# STM32F446RC_double_layer.net
KiCad netlist of a schematic drawn in EAGLE
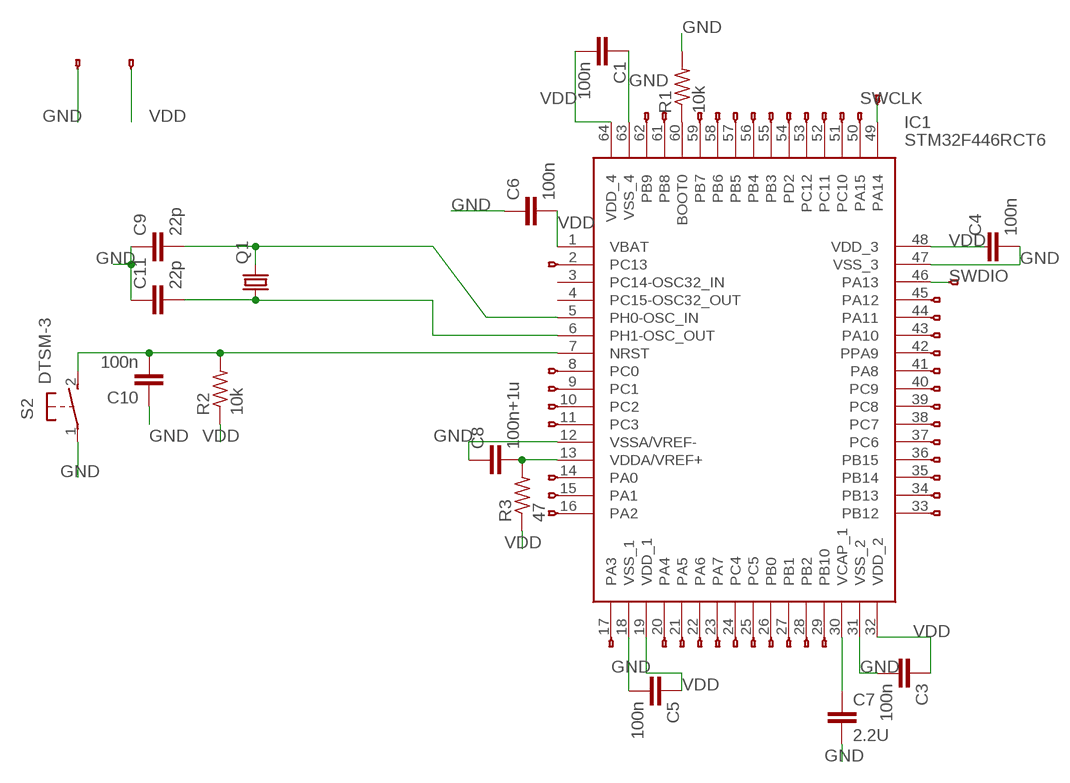
[diagram p0: schematic, sheet 1]

(export (version "E")
  (design (tool "Eeschema 10.0.6"))
  (components
    (comp (ref "C1")
      (value "100n")
      (footprint "eagle-import:C2.5-3")
      (libsource (lib "eagle-import") (part "C2,5-3"))
    )
    (comp (ref "C3")
      (value "100n")
      (footprint "eagle-import:C2.5-3")
      (libsource (lib "eagle-import") (part "C2,5-3"))
    )
    (comp (ref "C4")
      (value "100n")
      (footprint "eagle-import:C2.5-3")
      (libsource (lib "eagle-import") (part "C2,5-3"))
    )
    (comp (ref "C5")
      (value "100n")
      (footprint "eagle-import:C2.5-3")
      (libsource (lib "eagle-import") (part "C2,5-3"))
    )
    (comp (ref "C6")
      (value "100n")
      (footprint "eagle-import:C2.5-3")
      (libsource (lib "eagle-import") (part "C2,5-3"))
    )
    (comp (ref "C7")
      (value "2.2U")
      (footprint "eagle-import:C2.5-3")
      (libsource (lib "eagle-import") (part "C2,5-3"))
    )
    (comp (ref "C8")
      (value "100n+1u")
      (footprint "eagle-import:C2.5-3")
      (libsource (lib "eagle-import") (part "C2,5-3"))
    )
    (comp (ref "C9")
      (value "22p")
      (footprint "eagle-import:C2.5-3")
      (libsource (lib "eagle-import") (part "C2,5-3"))
    )
    (comp (ref "C10")
      (value "100n")
      (footprint "eagle-import:C2.5-3")
      (libsource (lib "eagle-import") (part "C2,5-3"))
    )
    (comp (ref "C11")
      (value "22p")
      (footprint "eagle-import:C2.5-3")
      (libsource (lib "eagle-import") (part "C2,5-3"))
    )
    (comp (ref "IC1")
      (value "STM32F446RCT6")
      (footprint "eagle-import:QFP50P1200X1200X160-64N")
      (fields (field (name "MOUSER_PART_NUMBER") "511-STM32F446RCT6"))
      (libsource (lib "eagle-import") (part "STM32F446RCT6"))
    )
    (comp (ref "JP1")
      (value "HEADERHOLE-HEADERHOLE")
      (footprint "eagle-import:1X1-HEADER-HOLE")
      (libsource (lib "eagle-import") (part "HEADERHOLE-HEADERHOLE"))
    )
    (comp (ref "JP2")
      (value "HEADERHOLE-HEADERHOLE")
      (footprint "eagle-import:1X1-HEADER-HOLE")
      (libsource (lib "eagle-import") (part "HEADERHOLE-HEADERHOLE"))
    )
    (comp (ref "JP3")
      (value "HEADERHOLE-HEADERHOLE")
      (footprint "eagle-import:1X1-HEADER-HOLE")
      (libsource (lib "eagle-import") (part "HEADERHOLE-HEADERHOLE"))
    )
    (comp (ref "JP4")
      (value "HEADERHOLE-HEADERHOLE")
      (footprint "eagle-import:1X1-HEADER-HOLE")
      (libsource (lib "eagle-import") (part "HEADERHOLE-HEADERHOLE"))
    )
    (comp (ref "JP5")
      (value "HEADERHOLE-HEADERHOLE")
      (footprint "eagle-import:1X1-HEADER-HOLE")
      (libsource (lib "eagle-import") (part "HEADERHOLE-HEADERHOLE"))
    )
    (comp (ref "JP6")
      (value "HEADERHOLE-HEADERHOLE")
      (footprint "eagle-import:1X1-HEADER-HOLE")
      (libsource (lib "eagle-import") (part "HEADERHOLE-HEADERHOLE"))
    )
    (comp (ref "JP7")
      (value "HEADERHOLE-HEADERHOLE")
      (footprint "eagle-import:1X1-HEADER-HOLE")
      (libsource (lib "eagle-import") (part "HEADERHOLE-HEADERHOLE"))
    )
    (comp (ref "JP8")
      (value "HEADERHOLE-HEADERHOLE")
      (footprint "eagle-import:1X1-HEADER-HOLE")
      (libsource (lib "eagle-import") (part "HEADERHOLE-HEADERHOLE"))
    )
    (comp (ref "JP9")
      (value "HEADERHOLE-HEADERHOLE")
      (footprint "eagle-import:1X1-HEADER-HOLE")
      (libsource (lib "eagle-import") (part "HEADERHOLE-HEADERHOLE"))
    )
    (comp (ref "JP10")
      (value "HEADERHOLE-HEADERHOLE")
      (footprint "eagle-import:1X1-HEADER-HOLE")
      (libsource (lib "eagle-import") (part "HEADERHOLE-HEADERHOLE"))
    )
    (comp (ref "JP11")
      (value "HEADERHOLE-HEADERHOLE")
      (footprint "eagle-import:1X1-HEADER-HOLE")
      (libsource (lib "eagle-import") (part "HEADERHOLE-HEADERHOLE"))
    )
    (comp (ref "JP12")
      (value "HEADERHOLE-HEADERHOLE")
      (footprint "eagle-import:1X1-HEADER-HOLE")
      (libsource (lib "eagle-import") (part "HEADERHOLE-HEADERHOLE"))
    )
    (comp (ref "JP13")
      (value "HEADERHOLE-HEADERHOLE")
      (footprint "eagle-import:1X1-HEADER-HOLE")
      (libsource (lib "eagle-import") (part "HEADERHOLE-HEADERHOLE"))
    )
    (comp (ref "JP14")
      (value "HEADERHOLE-HEADERHOLE")
      (footprint "eagle-import:1X1-HEADER-HOLE")
      (libsource (lib "eagle-import") (part "HEADERHOLE-HEADERHOLE"))
    )
    (comp (ref "JP15")
      (value "HEADERHOLE-HEADERHOLE")
      (footprint "eagle-import:1X1-HEADER-HOLE")
      (libsource (lib "eagle-import") (part "HEADERHOLE-HEADERHOLE"))
    )
    (comp (ref "JP16")
      (value "HEADERHOLE-HEADERHOLE")
      (footprint "eagle-import:1X1-HEADER-HOLE")
      (libsource (lib "eagle-import") (part "HEADERHOLE-HEADERHOLE"))
    )
    (comp (ref "JP17")
      (value "HEADERHOLE-HEADERHOLE")
      (footprint "eagle-import:1X1-HEADER-HOLE")
      (libsource (lib "eagle-import") (part "HEADERHOLE-HEADERHOLE"))
    )
    (comp (ref "JP18")
      (value "HEADERHOLE-HEADERHOLE")
      (footprint "eagle-import:1X1-HEADER-HOLE")
      (libsource (lib "eagle-import") (part "HEADERHOLE-HEADERHOLE"))
    )
    (comp (ref "JP19")
      (value "HEADERHOLE-HEADERHOLE")
      (footprint "eagle-import:1X1-HEADER-HOLE")
      (libsource (lib "eagle-import") (part "HEADERHOLE-HEADERHOLE"))
    )
    (comp (ref "JP21")
      (value "HEADERHOLE-HEADERHOLE")
      (footprint "eagle-import:1X1-HEADER-HOLE")
      (libsource (lib "eagle-import") (part "HEADERHOLE-HEADERHOLE"))
    )
    (comp (ref "JP22")
      (value "HEADERHOLE-HEADERHOLE")
      (footprint "eagle-import:1X1-HEADER-HOLE")
      (libsource (lib "eagle-import") (part "HEADERHOLE-HEADERHOLE"))
    )
    (comp (ref "JP23")
      (value "HEADERHOLE-HEADERHOLE")
      (footprint "eagle-import:1X1-HEADER-HOLE")
      (libsource (lib "eagle-import") (part "HEADERHOLE-HEADERHOLE"))
    )
    (comp (ref "JP24")
      (value "HEADERHOLE-HEADERHOLE")
      (footprint "eagle-import:1X1-HEADER-HOLE")
      (libsource (lib "eagle-import") (part "HEADERHOLE-HEADERHOLE"))
    )
    (comp (ref "JP25")
      (value "HEADERHOLE-HEADERHOLE")
      (footprint "eagle-import:1X1-HEADER-HOLE")
      (libsource (lib "eagle-import") (part "HEADERHOLE-HEADERHOLE"))
    )
    (comp (ref "JP26")
      (value "HEADERHOLE-HEADERHOLE")
      (footprint "eagle-import:1X1-HEADER-HOLE")
      (libsource (lib "eagle-import") (part "HEADERHOLE-HEADERHOLE"))
    )
    (comp (ref "JP27")
      (value "HEADERHOLE-HEADERHOLE")
      (footprint "eagle-import:1X1-HEADER-HOLE")
      (libsource (lib "eagle-import") (part "HEADERHOLE-HEADERHOLE"))
    )
    (comp (ref "JP28")
      (value "HEADERHOLE-HEADERHOLE")
      (footprint "eagle-import:1X1-HEADER-HOLE")
      (libsource (lib "eagle-import") (part "HEADERHOLE-HEADERHOLE"))
    )
    (comp (ref "JP29")
      (value "HEADERHOLE-HEADERHOLE")
      (footprint "eagle-import:1X1-HEADER-HOLE")
      (libsource (lib "eagle-import") (part "HEADERHOLE-HEADERHOLE"))
    )
    (comp (ref "JP30")
      (value "HEADERHOLE-HEADERHOLE")
      (footprint "eagle-import:1X1-HEADER-HOLE")
      (libsource (lib "eagle-import") (part "HEADERHOLE-HEADERHOLE"))
    )
    (comp (ref "JP31")
      (value "HEADERHOLE-HEADERHOLE")
      (footprint "eagle-import:1X1-HEADER-HOLE")
      (libsource (lib "eagle-import") (part "HEADERHOLE-HEADERHOLE"))
    )
    (comp (ref "JP32")
      (value "HEADERHOLE-HEADERHOLE")
      (footprint "eagle-import:1X1-HEADER-HOLE")
      (libsource (lib "eagle-import") (part "HEADERHOLE-HEADERHOLE"))
    )
    (comp (ref "JP33")
      (value "HEADERHOLE-HEADERHOLE")
      (footprint "eagle-import:1X1-HEADER-HOLE")
      (libsource (lib "eagle-import") (part "HEADERHOLE-HEADERHOLE"))
    )
    (comp (ref "JP34")
      (value "HEADERHOLE-HEADERHOLE")
      (footprint "eagle-import:1X1-HEADER-HOLE")
      (libsource (lib "eagle-import") (part "HEADERHOLE-HEADERHOLE"))
    )
    (comp (ref "JP35")
      (value "HEADERHOLE-HEADERHOLE")
      (footprint "eagle-import:1X1-HEADER-HOLE")
      (libsource (lib "eagle-import") (part "HEADERHOLE-HEADERHOLE"))
    )
    (comp (ref "JP36")
      (value "HEADERHOLE-HEADERHOLE")
      (footprint "eagle-import:1X1-HEADER-HOLE")
      (libsource (lib "eagle-import") (part "HEADERHOLE-HEADERHOLE"))
    )
    (comp (ref "JP37")
      (value "HEADERHOLE-HEADERHOLE")
      (footprint "eagle-import:1X1-HEADER-HOLE")
      (libsource (lib "eagle-import") (part "HEADERHOLE-HEADERHOLE"))
    )
    (comp (ref "JP38")
      (value "HEADERHOLE-HEADERHOLE")
      (footprint "eagle-import:1X1-HEADER-HOLE")
      (libsource (lib "eagle-import") (part "HEADERHOLE-HEADERHOLE"))
    )
    (comp (ref "JP39")
      (value "HEADERHOLE-HEADERHOLE")
      (footprint "eagle-import:1X1-HEADER-HOLE")
      (libsource (lib "eagle-import") (part "HEADERHOLE-HEADERHOLE"))
    )
    (comp (ref "JP40")
      (value "HEADERHOLE-HEADERHOLE")
      (footprint "eagle-import:1X1-HEADER-HOLE")
      (libsource (lib "eagle-import") (part "HEADERHOLE-HEADERHOLE"))
    )
    (comp (ref "JP41")
      (value "HEADERHOLE-HEADERHOLE")
      (footprint "eagle-import:1X1-HEADER-HOLE")
      (libsource (lib "eagle-import") (part "HEADERHOLE-HEADERHOLE"))
    )
    (comp (ref "JP42")
      (value "HEADERHOLE-HEADERHOLE")
      (footprint "eagle-import:1X1-HEADER-HOLE")
      (libsource (lib "eagle-import") (part "HEADERHOLE-HEADERHOLE"))
    )
    (comp (ref "JP43")
      (value "HEADERHOLE-HEADERHOLE")
      (footprint "eagle-import:1X1-HEADER-HOLE")
      (libsource (lib "eagle-import") (part "HEADERHOLE-HEADERHOLE"))
    )
    (comp (ref "JP44")
      (value "HEADERHOLE-HEADERHOLE")
      (footprint "eagle-import:1X1-HEADER-HOLE")
      (libsource (lib "eagle-import") (part "HEADERHOLE-HEADERHOLE"))
    )
    (comp (ref "JP45")
      (value "HEADERHOLE-HEADERHOLE")
      (footprint "eagle-import:1X1-HEADER-HOLE")
      (libsource (lib "eagle-import") (part "HEADERHOLE-HEADERHOLE"))
    )
    (comp (ref "JP46")
      (value "HEADERHOLE-HEADERHOLE")
      (footprint "eagle-import:1X1-HEADER-HOLE")
      (libsource (lib "eagle-import") (part "HEADERHOLE-HEADERHOLE"))
    )
    (comp (ref "JP47")
      (value "HEADERHOLE-HEADERHOLE")
      (footprint "eagle-import:1X1-HEADER-HOLE")
      (libsource (lib "eagle-import") (part "HEADERHOLE-HEADERHOLE"))
    )
    (comp (ref "JP54")
      (value "HEADERHOLE-HEADERHOLE")
      (footprint "eagle-import:1X1-HEADER-HOLE")
      (libsource (lib "eagle-import") (part "HEADERHOLE-HEADERHOLE"))
    )
    (comp (ref "JP55")
      (value "HEADERHOLE-HEADERHOLE")
      (footprint "eagle-import:1X1-HEADER-HOLE")
      (libsource (lib "eagle-import") (part "HEADERHOLE-HEADERHOLE"))
    )
    (comp (ref "Q1")
      (value "CRYSTALHC49S")
      (footprint "eagle-import:HC49_S")
      (libsource (lib "eagle-import") (part "CRYSTALHC49S"))
    )
    (comp (ref "R1")
      (value "10k")
      (footprint "eagle-import:0204V")
      (libsource (lib "eagle-import") (part "R-US_0204/2V"))
    )
    (comp (ref "R2")
      (value "10k")
      (footprint "eagle-import:0204V")
      (libsource (lib "eagle-import") (part "R-US_0204/2V"))
    )
    (comp (ref "R3")
      (value "47")
      (footprint "eagle-import:0204V")
      (libsource (lib "eagle-import") (part "R-US_0204/2V"))
    )
    (comp (ref "S2")
      (value "DTSM-3")
      (footprint "eagle-import:DTSM-3")
      (libsource (lib "eagle-import") (part "DTSM-3"))
    )
  )
  (nets
    (net (code "1") (name "/GND") (class "Default")
      (node (ref "C1") (pin "1") (pinfunction "1_1") (pintype "passive"))
      (node (ref "C10") (pin "1") (pinfunction "1_1") (pintype "passive"))
      (node (ref "C11") (pin "1") (pinfunction "1_1") (pintype "passive"))
      (node (ref "C3") (pin "2") (pinfunction "2_2") (pintype "passive"))
      (node (ref "C4") (pin "2") (pinfunction "2_2") (pintype "passive"))
      (node (ref "C5") (pin "2") (pinfunction "2_2") (pintype "passive"))
      (node (ref "C6") (pin "1") (pinfunction "1_1") (pintype "passive"))
      (node (ref "C7") (pin "2") (pinfunction "2_2") (pintype "passive"))
      (node (ref "C8") (pin "1") (pinfunction "1_1") (pintype "passive"))
      (node (ref "C9") (pin "1") (pinfunction "1_1") (pintype "passive"))
      (node (ref "IC1") (pin "12") (pinfunction "VSSA/VREF-_12") (pintype "bidirectional"))
      (node (ref "IC1") (pin "18") (pinfunction "VSS_1_18") (pintype "bidirectional"))
      (node (ref "IC1") (pin "31") (pinfunction "VSS_2_31") (pintype "bidirectional"))
      (node (ref "IC1") (pin "47") (pinfunction "VSS_3_47") (pintype "bidirectional"))
      (node (ref "IC1") (pin "63") (pinfunction "VSS_4_63") (pintype "bidirectional"))
      (node (ref "JP7") (pin "1") (pinfunction "P$1_1") (pintype "bidirectional"))
      (node (ref "R1") (pin "2") (pinfunction "2_2") (pintype "passive"))
      (node (ref "S2") (pin "1") (pinfunction "1_1") (pintype "passive"))
    )
    (net (code "2") (name "/SWCLK") (class "Default")
      (node (ref "IC1") (pin "49") (pinfunction "PA14_49") (pintype "bidirectional"))
      (node (ref "JP55") (pin "1") (pinfunction "P$1_1") (pintype "bidirectional"))
    )
    (net (code "3") (name "/SWDIO") (class "Default")
      (node (ref "IC1") (pin "46") (pinfunction "PA13_46") (pintype "bidirectional"))
      (node (ref "JP54") (pin "1") (pinfunction "P$1_1") (pintype "bidirectional"))
    )
    (net (code "4") (name "/VDD") (class "Default")
      (node (ref "C1") (pin "2") (pinfunction "2_2") (pintype "passive"))
      (node (ref "C3") (pin "1") (pinfunction "1_1") (pintype "passive"))
      (node (ref "C4") (pin "1") (pinfunction "1_1") (pintype "passive"))
      (node (ref "C5") (pin "1") (pinfunction "1_1") (pintype "passive"))
      (node (ref "C6") (pin "2") (pinfunction "2_2") (pintype "passive"))
      (node (ref "IC1") (pin "1") (pinfunction "VBAT_1") (pintype "bidirectional"))
      (node (ref "IC1") (pin "19") (pinfunction "VDD_1_19") (pintype "bidirectional"))
      (node (ref "IC1") (pin "32") (pinfunction "VDD_2_32") (pintype "bidirectional"))
      (node (ref "IC1") (pin "48") (pinfunction "VDD_3_48") (pintype "bidirectional"))
      (node (ref "IC1") (pin "64") (pinfunction "VDD_4_64") (pintype "bidirectional"))
      (node (ref "JP8") (pin "1") (pinfunction "P$1_1") (pintype "bidirectional"))
      (node (ref "R2") (pin "1") (pinfunction "1_1") (pintype "passive"))
      (node (ref "R3") (pin "1") (pinfunction "1_1") (pintype "passive"))
    )
    (net (code "5") (name "Net-(IC1-BOOT0)") (class "Default")
      (node (ref "IC1") (pin "60") (pinfunction "BOOT0_60") (pintype "bidirectional"))
      (node (ref "R1") (pin "1") (pinfunction "1_1") (pintype "passive"))
    )
    (net (code "6") (name "Net-(IC1-NRST)") (class "Default")
      (node (ref "C10") (pin "2") (pinfunction "2_2") (pintype "passive"))
      (node (ref "IC1") (pin "7") (pinfunction "NRST_7") (pintype "bidirectional"))
      (node (ref "R2") (pin "2") (pinfunction "2_2") (pintype "passive"))
      (node (ref "S2") (pin "2") (pinfunction "2_2") (pintype "passive"))
    )
    (net (code "7") (name "Net-(IC1-PA0)") (class "Default")
      (node (ref "IC1") (pin "14") (pinfunction "PA0_14") (pintype "bidirectional"))
      (node (ref "JP34") (pin "1") (pinfunction "P$1_1") (pintype "bidirectional"))
    )
    (net (code "8") (name "Net-(IC1-PA1)") (class "Default")
      (node (ref "IC1") (pin "15") (pinfunction "PA1_15") (pintype "bidirectional"))
      (node (ref "JP35") (pin "1") (pinfunction "P$1_1") (pintype "bidirectional"))
    )
    (net (code "9") (name "Net-(IC1-PA2)") (class "Default")
      (node (ref "IC1") (pin "16") (pinfunction "PA2_16") (pintype "bidirectional"))
      (node (ref "JP36") (pin "1") (pinfunction "P$1_1") (pintype "bidirectional"))
    )
    (net (code "10") (name "Net-(IC1-PA3)") (class "Default")
      (node (ref "IC1") (pin "17") (pinfunction "PA3_17") (pintype "bidirectional"))
      (node (ref "JP24") (pin "1") (pinfunction "P$1_1") (pintype "bidirectional"))
    )
    (net (code "11") (name "Net-(IC1-PA4)") (class "Default")
      (node (ref "IC1") (pin "20") (pinfunction "PA4_20") (pintype "bidirectional"))
      (node (ref "JP21") (pin "1") (pinfunction "P$1_1") (pintype "bidirectional"))
    )
    (net (code "12") (name "Net-(IC1-PA5)") (class "Default")
      (node (ref "IC1") (pin "21") (pinfunction "PA5_21") (pintype "bidirectional"))
      (node (ref "JP19") (pin "1") (pinfunction "P$1_1") (pintype "bidirectional"))
    )
    (net (code "13") (name "Net-(IC1-PA6)") (class "Default")
      (node (ref "IC1") (pin "22") (pinfunction "PA6_22") (pintype "bidirectional"))
      (node (ref "JP9") (pin "1") (pinfunction "P$1_1") (pintype "bidirectional"))
    )
    (net (code "14") (name "Net-(IC1-PA7)") (class "Default")
      (node (ref "IC1") (pin "23") (pinfunction "PA7_23") (pintype "bidirectional"))
      (node (ref "JP11") (pin "1") (pinfunction "P$1_1") (pintype "bidirectional"))
    )
    (net (code "15") (name "Net-(IC1-PA8)") (class "Default")
      (node (ref "IC1") (pin "41") (pinfunction "PA8_41") (pintype "bidirectional"))
      (node (ref "JP28") (pin "1") (pinfunction "P$1_1") (pintype "bidirectional"))
    )
    (net (code "16") (name "Net-(IC1-PA10)") (class "Default")
      (node (ref "IC1") (pin "43") (pinfunction "PA10_43") (pintype "bidirectional"))
      (node (ref "JP33") (pin "1") (pinfunction "P$1_1") (pintype "bidirectional"))
    )
    (net (code "17") (name "Net-(IC1-PA11)") (class "Default")
      (node (ref "IC1") (pin "44") (pinfunction "PA11_44") (pintype "bidirectional"))
      (node (ref "JP32") (pin "1") (pinfunction "P$1_1") (pintype "bidirectional"))
    )
    (net (code "18") (name "Net-(IC1-PA12)") (class "Default")
      (node (ref "IC1") (pin "45") (pinfunction "PA12_45") (pintype "bidirectional"))
      (node (ref "JP25") (pin "1") (pinfunction "P$1_1") (pintype "bidirectional"))
    )
    (net (code "19") (name "Net-(IC1-PA15)") (class "Default")
      (node (ref "IC1") (pin "50") (pinfunction "PA15_50") (pintype "bidirectional"))
      (node (ref "JP45") (pin "1") (pinfunction "P$1_1") (pintype "bidirectional"))
    )
    (net (code "20") (name "Net-(IC1-PB0)") (class "Default")
      (node (ref "IC1") (pin "26") (pinfunction "PB0_26") (pintype "bidirectional"))
      (node (ref "JP22") (pin "1") (pinfunction "P$1_1") (pintype "bidirectional"))
    )
    (net (code "21") (name "Net-(IC1-PB1)") (class "Default")
      (node (ref "IC1") (pin "27") (pinfunction "PB1_27") (pintype "bidirectional"))
      (node (ref "JP17") (pin "1") (pinfunction "P$1_1") (pintype "bidirectional"))
    )
    (net (code "22") (name "Net-(IC1-PB2)") (class "Default")
      (node (ref "IC1") (pin "28") (pinfunction "PB2_28") (pintype "bidirectional"))
      (node (ref "JP16") (pin "1") (pinfunction "P$1_1") (pintype "bidirectional"))
    )
    (net (code "23") (name "Net-(IC1-PB3)") (class "Default")
      (node (ref "IC1") (pin "55") (pinfunction "PB3_55") (pintype "bidirectional"))
      (node (ref "JP44") (pin "1") (pinfunction "P$1_1") (pintype "bidirectional"))
    )
    (net (code "24") (name "Net-(IC1-PB4)") (class "Default")
      (node (ref "IC1") (pin "56") (pinfunction "PB4_56") (pintype "bidirectional"))
      (node (ref "JP40") (pin "1") (pinfunction "P$1_1") (pintype "bidirectional"))
    )
    (net (code "25") (name "Net-(IC1-PB5)") (class "Default")
      (node (ref "IC1") (pin "57") (pinfunction "PB5_57") (pintype "bidirectional"))
      (node (ref "JP41") (pin "1") (pinfunction "P$1_1") (pintype "bidirectional"))
    )
    (net (code "26") (name "Net-(IC1-PB6)") (class "Default")
      (node (ref "IC1") (pin "58") (pinfunction "PB6_58") (pintype "bidirectional"))
      (node (ref "JP42") (pin "1") (pinfunction "P$1_1") (pintype "bidirectional"))
    )
    (net (code "27") (name "Net-(IC1-PB7)") (class "Default")
      (node (ref "IC1") (pin "59") (pinfunction "PB7_59") (pintype "bidirectional"))
      (node (ref "JP43") (pin "1") (pinfunction "P$1_1") (pintype "bidirectional"))
    )
    (net (code "28") (name "Net-(IC1-PB8)") (class "Default")
      (node (ref "IC1") (pin "61") (pinfunction "PB8_61") (pintype "bidirectional"))
      (node (ref "JP46") (pin "1") (pinfunction "P$1_1") (pintype "bidirectional"))
    )
    (net (code "29") (name "Net-(IC1-PB9)") (class "Default")
      (node (ref "IC1") (pin "62") (pinfunction "PB9_62") (pintype "bidirectional"))
      (node (ref "JP47") (pin "1") (pinfunction "P$1_1") (pintype "bidirectional"))
    )
    (net (code "30") (name "Net-(IC1-PB10)") (class "Default")
      (node (ref "IC1") (pin "29") (pinfunction "PB10_29") (pintype "bidirectional"))
      (node (ref "JP14") (pin "1") (pinfunction "P$1_1") (pintype "bidirectional"))
    )
    (net (code "31") (name "Net-(IC1-PB12)") (class "Default")
      (node (ref "IC1") (pin "33") (pinfunction "PB12_33") (pintype "bidirectional"))
      (node (ref "JP18") (pin "1") (pinfunction "P$1_1") (pintype "bidirectional"))
    )
    (net (code "32") (name "Net-(IC1-PB13)") (class "Default")
      (node (ref "IC1") (pin "34") (pinfunction "PB13_34") (pintype "bidirectional"))
      (node (ref "JP13") (pin "1") (pinfunction "P$1_1") (pintype "bidirectional"))
    )
    (net (code "33") (name "Net-(IC1-PB14)") (class "Default")
      (node (ref "IC1") (pin "35") (pinfunction "PB14_35") (pintype "bidirectional"))
      (node (ref "JP6") (pin "1") (pinfunction "P$1_1") (pintype "bidirectional"))
    )
    (net (code "34") (name "Net-(IC1-PB15)") (class "Default")
      (node (ref "IC1") (pin "36") (pinfunction "PB15_36") (pintype "bidirectional"))
      (node (ref "JP10") (pin "1") (pinfunction "P$1_1") (pintype "bidirectional"))
    )
    (net (code "35") (name "Net-(IC1-PC0)") (class "Default")
      (node (ref "IC1") (pin "8") (pinfunction "PC0_8") (pintype "bidirectional"))
      (node (ref "JP29") (pin "1") (pinfunction "P$1_1") (pintype "bidirectional"))
    )
    (net (code "36") (name "Net-(IC1-PC1)") (class "Default")
      (node (ref "IC1") (pin "9") (pinfunction "PC1_9") (pintype "bidirectional"))
      (node (ref "JP27") (pin "1") (pinfunction "P$1_1") (pintype "bidirectional"))
    )
    (net (code "37") (name "Net-(IC1-PC2)") (class "Default")
      (node (ref "IC1") (pin "10") (pinfunction "PC2_10") (pintype "bidirectional"))
      (node (ref "JP3") (pin "1") (pinfunction "P$1_1") (pintype "bidirectional"))
    )
    (net (code "38") (name "Net-(IC1-PC3)") (class "Default")
      (node (ref "IC1") (pin "11") (pinfunction "PC3_11") (pintype "bidirectional"))
      (node (ref "JP4") (pin "1") (pinfunction "P$1_1") (pintype "bidirectional"))
    )
    (net (code "39") (name "Net-(IC1-PC4)") (class "Default")
      (node (ref "IC1") (pin "24") (pinfunction "PC4_24") (pintype "bidirectional"))
      (node (ref "JP12") (pin "1") (pinfunction "P$1_1") (pintype "bidirectional"))
    )
    (net (code "40") (name "Net-(IC1-PC5)") (class "Default")
      (node (ref "IC1") (pin "25") (pinfunction "PC5_25") (pintype "bidirectional"))
      (node (ref "JP23") (pin "1") (pinfunction "P$1_1") (pintype "bidirectional"))
    )
    (net (code "41") (name "Net-(IC1-PC6)") (class "Default")
      (node (ref "IC1") (pin "37") (pinfunction "PC6_37") (pintype "bidirectional"))
      (node (ref "JP1") (pin "1") (pinfunction "P$1_1") (pintype "bidirectional"))
    )
    (net (code "42") (name "Net-(IC1-PC7)") (class "Default")
      (node (ref "IC1") (pin "38") (pinfunction "PC7_38") (pintype "bidirectional"))
      (node (ref "JP15") (pin "1") (pinfunction "P$1_1") (pintype "bidirectional"))
    )
    (net (code "43") (name "Net-(IC1-PC8)") (class "Default")
      (node (ref "IC1") (pin "39") (pinfunction "PC8_39") (pintype "bidirectional"))
      (node (ref "JP2") (pin "1") (pinfunction "P$1_1") (pintype "bidirectional"))
    )
    (net (code "44") (name "Net-(IC1-PC9)") (class "Default")
      (node (ref "IC1") (pin "40") (pinfunction "PC9_40") (pintype "bidirectional"))
      (node (ref "JP30") (pin "1") (pinfunction "P$1_1") (pintype "bidirectional"))
    )
    (net (code "45") (name "Net-(IC1-PC10)") (class "Default")
      (node (ref "IC1") (pin "51") (pinfunction "PC10_51") (pintype "bidirectional"))
      (node (ref "JP37") (pin "1") (pinfunction "P$1_1") (pintype "bidirectional"))
    )
    (net (code "46") (name "Net-(IC1-PC11)") (class "Default")
      (node (ref "IC1") (pin "52") (pinfunction "PC11_52") (pintype "bidirectional"))
      (node (ref "JP5") (pin "1") (pinfunction "P$1_1") (pintype "bidirectional"))
    )
    (net (code "47") (name "Net-(IC1-PC12)") (class "Default")
      (node (ref "IC1") (pin "53") (pinfunction "PC12_53") (pintype "bidirectional"))
      (node (ref "JP39") (pin "1") (pinfunction "P$1_1") (pintype "bidirectional"))
    )
    (net (code "48") (name "Net-(IC1-PC13)") (class "Default")
      (node (ref "IC1") (pin "2") (pinfunction "PC13_2") (pintype "bidirectional"))
      (node (ref "JP26") (pin "1") (pinfunction "P$1_1") (pintype "bidirectional"))
    )
    (net (code "49") (name "Net-(IC1-PD2)") (class "Default")
      (node (ref "IC1") (pin "54") (pinfunction "PD2_54") (pintype "bidirectional"))
      (node (ref "JP38") (pin "1") (pinfunction "P$1_1") (pintype "bidirectional"))
    )
    (net (code "50") (name "Net-(IC1-PH0-OSC_IN)") (class "Default")
      (node (ref "C9") (pin "2") (pinfunction "2_2") (pintype "passive"))
      (node (ref "IC1") (pin "5") (pinfunction "PH0-OSC_IN_5") (pintype "bidirectional"))
      (node (ref "Q1") (pin "2") (pinfunction "2_2") (pintype "passive"))
    )
    (net (code "51") (name "Net-(IC1-PH1-OSC_OUT)") (class "Default")
      (node (ref "C11") (pin "2") (pinfunction "2_2") (pintype "passive"))
      (node (ref "IC1") (pin "6") (pinfunction "PH1-OSC_OUT_6") (pintype "bidirectional"))
      (node (ref "Q1") (pin "1") (pinfunction "1_1") (pintype "passive"))
    )
    (net (code "52") (name "Net-(IC1-PPA9)") (class "Default")
      (node (ref "IC1") (pin "42") (pinfunction "PPA9_42") (pintype "bidirectional"))
      (node (ref "JP31") (pin "1") (pinfunction "P$1_1") (pintype "bidirectional"))
    )
    (net (code "53") (name "Net-(IC1-VCAP_1)") (class "Default")
      (node (ref "C7") (pin "1") (pinfunction "1_1") (pintype "passive"))
      (node (ref "IC1") (pin "30") (pinfunction "VCAP_1_30") (pintype "bidirectional"))
    )
    (net (code "54") (name "Net-(IC1-VDDA{slash}VREF+)") (class "Default")
      (node (ref "C8") (pin "2") (pinfunction "2_2") (pintype "passive"))
      (node (ref "IC1") (pin "13") (pinfunction "VDDA/VREF+_13") (pintype "bidirectional"))
      (node (ref "R3") (pin "2") (pinfunction "2_2") (pintype "passive"))
    )
    (net (code "55") (name "unconnected-(IC1-PC14-OSC32_IN-Pad3)") (class "Default")
      (node (ref "IC1") (pin "3") (pinfunction "PC14-OSC32_IN_3") (pintype "bidirectional"))
    )
    (net (code "56") (name "unconnected-(IC1-PC15-OSC32_OUT-Pad4)") (class "Default")
      (node (ref "IC1") (pin "4") (pinfunction "PC15-OSC32_OUT_4") (pintype "bidirectional"))
    )
  )
)
